# AC225-16A-MHCW05P-B_V1_0.net
KiCad netlist of a schematic drawn in Altium Designer
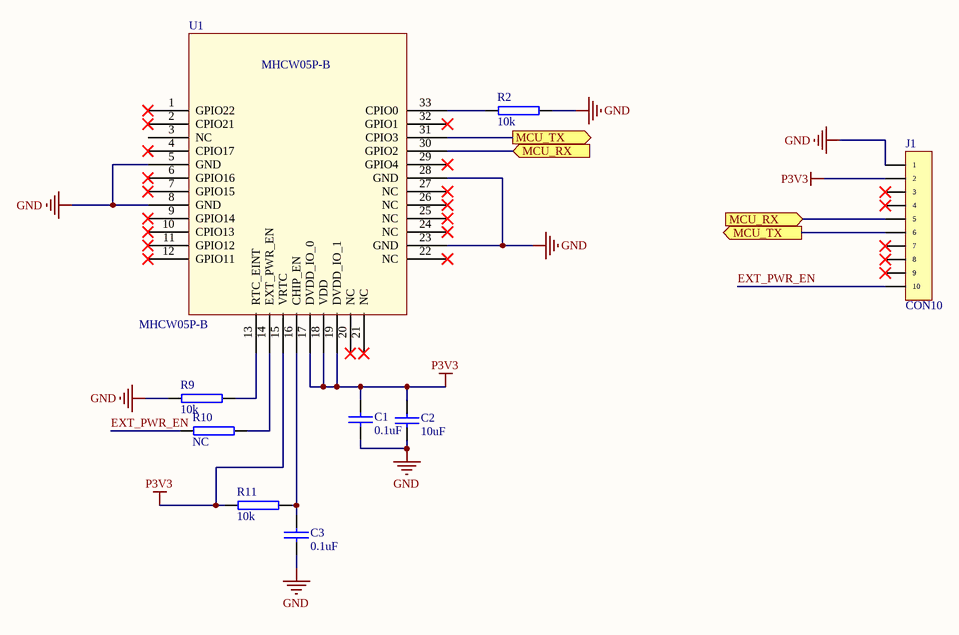
[diagram p0: AC225-16A-MHCW05P-B_V1.0.SchDoc]

(export (version "E")
  (design (tool "Eeschema 10.0.6"))
  (components
    (comp (ref "C1") (value "0.1uF") (footprint "C-0603") (libsource (lib "AOK 原理图库2020") (part "CAP")))
    (comp (ref "C2") (value "10uF") (footprint "C-0603") (libsource (lib "AOK 原理图库2020") (part "CAP")))
    (comp (ref "C3") (value "0.1uF") (footprint "C-0603") (libsource (lib "AOK 原理图库2020") (part "CAP")))
    (comp (ref "J1") (value "CON10") (footprint "DIP_10") (libsource (lib "AOK 原理图库2020") (part "CON10")))
    (comp (ref "R2") (value "10k") (footprint "R-0603") (libsource (lib "AOK 原理图库2020") (part "RES2")))
    (comp (ref "R9") (value "10k") (footprint "R-0603") (libsource (lib "AOK 原理图库2020") (part "RES2")))
    (comp (ref "R10") (value "NC") (footprint "R-0603") (libsource (lib "AOK 原理图库2020") (part "RES2")))
    (comp (ref "R11") (value "10k") (footprint "R-0603") (libsource (lib "AOK 原理图库2020") (part "RES2")))
    (comp (ref "U1")
      (value "MHCW05P-B")
      (footprint "MHCW05P-B")
      (libsource (lib "AOK 原理图库2020") (part "MHCW05P-B"))
    )
  )
  (nets
    (net (code "1") (name "/EXT_PWR_EN") (class "Default")
      (node (ref "J1") (pin "10") (pinfunction "10_10") (pintype "passive"))
      (node (ref "R10") (pin "2") (pinfunction "2_2") (pintype "passive"))
    )
    (net (code "2") (name "/MCU_RX") (class "Default")
      (node (ref "J1") (pin "5") (pinfunction "5_5") (pintype "passive"))
      (node (ref "U1") (pin "30") (pinfunction "GPIO2_30") (pintype "passive"))
    )
    (net (code "3") (name "/MCU_TX") (class "Default")
      (node (ref "J1") (pin "6") (pinfunction "6_6") (pintype "passive"))
      (node (ref "U1") (pin "31") (pinfunction "CPIO3_31") (pintype "passive"))
    )
    (net (code "4") (name "GND") (class "Default")
      (node (ref "C1") (pin "2") (pinfunction "2_2") (pintype "passive"))
      (node (ref "C2") (pin "2") (pinfunction "2_2") (pintype "passive"))
      (node (ref "C3") (pin "2") (pinfunction "2_2") (pintype "passive"))
      (node (ref "J1") (pin "1") (pinfunction "1_1") (pintype "passive"))
      (node (ref "R2") (pin "1") (pinfunction "1_1") (pintype "passive"))
      (node (ref "R9") (pin "2") (pinfunction "2_2") (pintype "passive"))
      (node (ref "U1") (pin "23") (pinfunction "GND_23") (pintype "passive"))
      (node (ref "U1") (pin "28") (pinfunction "GND_28") (pintype "passive"))
      (node (ref "U1") (pin "5") (pinfunction "GND_5") (pintype "passive"))
      (node (ref "U1") (pin "8") (pinfunction "GND_8") (pintype "passive"))
    )
    (net (code "5") (name "Net-(U1-CHIP_EN)") (class "Default")
      (node (ref "C3") (pin "1") (pinfunction "1_1") (pintype "passive"))
      (node (ref "R11") (pin "1") (pinfunction "1_1") (pintype "passive"))
      (node (ref "U1") (pin "16") (pinfunction "CHIP_EN_16") (pintype "passive"))
    )
    (net (code "6") (name "Net-(U1-CPIO0)") (class "Default")
      (node (ref "R2") (pin "2") (pinfunction "2_2") (pintype "passive"))
      (node (ref "U1") (pin "33") (pinfunction "CPIO0_33") (pintype "passive"))
    )
    (net (code "7") (name "Net-(U1-EXT_PWR_EN)") (class "Default")
      (node (ref "R10") (pin "1") (pinfunction "1_1") (pintype "passive"))
      (node (ref "U1") (pin "14") (pinfunction "EXT_PWR_EN_14") (pintype "passive"))
    )
    (net (code "8") (name "Net-(U1-RTC_EINT)") (class "Default")
      (node (ref "R9") (pin "1") (pinfunction "1_1") (pintype "passive"))
      (node (ref "U1") (pin "13") (pinfunction "RTC_EINT_13") (pintype "passive"))
    )
    (net (code "9") (name "P3V3") (class "Default")
      (node (ref "C1") (pin "1") (pinfunction "1_1") (pintype "passive"))
      (node (ref "C2") (pin "1") (pinfunction "1_1") (pintype "passive"))
      (node (ref "J1") (pin "2") (pinfunction "2_2") (pintype "passive"))
      (node (ref "R11") (pin "2") (pinfunction "2_2") (pintype "passive"))
      (node (ref "U1") (pin "15") (pinfunction "VRTC_15") (pintype "passive"))
      (node (ref "U1") (pin "17") (pinfunction "DVDD_IO_0_17") (pintype "passive"))
      (node (ref "U1") (pin "18") (pinfunction "VDD_18") (pintype "passive"))
      (node (ref "U1") (pin "19") (pinfunction "DVDD_IO_1_19") (pintype "passive"))
    )
    (net (code "10") (name "unconnected-(J1-Pad3)") (class "Default")
      (node (ref "J1") (pin "3") (pinfunction "3_3") (pintype "passive+no_connect"))
    )
    (net (code "11") (name "unconnected-(J1-Pad4)") (class "Default")
      (node (ref "J1") (pin "4") (pinfunction "4_4") (pintype "passive+no_connect"))
    )
    (net (code "12") (name "unconnected-(J1-Pad7)") (class "Default")
      (node (ref "J1") (pin "7") (pinfunction "7_7") (pintype "passive+no_connect"))
    )
    (net (code "13") (name "unconnected-(J1-Pad8)") (class "Default")
      (node (ref "J1") (pin "8") (pinfunction "8_8") (pintype "passive+no_connect"))
    )
    (net (code "14") (name "unconnected-(J1-Pad9)") (class "Default")
      (node (ref "J1") (pin "9") (pinfunction "9_9") (pintype "passive+no_connect"))
    )
    (net (code "15") (name "unconnected-(U1-CPIO13-Pad10)") (class "Default")
      (node (ref "U1") (pin "10") (pinfunction "CPIO13_10") (pintype "passive+no_connect"))
    )
    (net (code "16") (name "unconnected-(U1-CPIO17-Pad4)") (class "Default")
      (node (ref "U1") (pin "4") (pinfunction "CPIO17_4") (pintype "passive+no_connect"))
    )
    (net (code "17") (name "unconnected-(U1-CPIO21-Pad2)") (class "Default")
      (node (ref "U1") (pin "2") (pinfunction "CPIO21_2") (pintype "passive+no_connect"))
    )
    (net (code "18") (name "unconnected-(U1-GPIO1-Pad32)") (class "Default")
      (node (ref "U1") (pin "32") (pinfunction "GPIO1_32") (pintype "passive+no_connect"))
    )
    (net (code "19") (name "unconnected-(U1-GPIO4-Pad29)") (class "Default")
      (node (ref "U1") (pin "29") (pinfunction "GPIO4_29") (pintype "passive+no_connect"))
    )
    (net (code "20") (name "unconnected-(U1-GPIO11-Pad12)") (class "Default")
      (node (ref "U1") (pin "12") (pinfunction "GPIO11_12") (pintype "passive+no_connect"))
    )
    (net (code "21") (name "unconnected-(U1-GPIO12-Pad11)") (class "Default")
      (node (ref "U1") (pin "11") (pinfunction "GPIO12_11") (pintype "passive+no_connect"))
    )
    (net (code "22") (name "unconnected-(U1-GPIO14-Pad9)") (class "Default")
      (node (ref "U1") (pin "9") (pinfunction "GPIO14_9") (pintype "passive+no_connect"))
    )
    (net (code "23") (name "unconnected-(U1-GPIO15-Pad7)") (class "Default")
      (node (ref "U1") (pin "7") (pinfunction "GPIO15_7") (pintype "passive+no_connect"))
    )
    (net (code "24") (name "unconnected-(U1-GPIO16-Pad6)") (class "Default")
      (node (ref "U1") (pin "6") (pinfunction "GPIO16_6") (pintype "passive+no_connect"))
    )
    (net (code "25") (name "unconnected-(U1-GPIO22-Pad1)") (class "Default")
      (node (ref "U1") (pin "1") (pinfunction "GPIO22_1") (pintype "passive+no_connect"))
    )
    (net (code "26") (name "unconnected-(U1-NC-Pad3)") (class "Default")
      (node (ref "U1") (pin "3") (pinfunction "NC_3") (pintype "passive"))
    )
    (net (code "27") (name "unconnected-(U1-NC-Pad20)") (class "Default")
      (node (ref "U1") (pin "20") (pinfunction "NC_20") (pintype "passive+no_connect"))
    )
    (net (code "28") (name "unconnected-(U1-NC-Pad21)") (class "Default")
      (node (ref "U1") (pin "21") (pinfunction "NC_21") (pintype "passive+no_connect"))
    )
    (net (code "29") (name "unconnected-(U1-NC-Pad22)") (class "Default")
      (node (ref "U1") (pin "22") (pinfunction "NC_22") (pintype "passive+no_connect"))
    )
    (net (code "30") (name "unconnected-(U1-NC-Pad24)") (class "Default")
      (node (ref "U1") (pin "24") (pinfunction "NC_24") (pintype "passive+no_connect"))
    )
    (net (code "31") (name "unconnected-(U1-NC-Pad25)") (class "Default")
      (node (ref "U1") (pin "25") (pinfunction "NC_25") (pintype "passive+no_connect"))
    )
    (net (code "32") (name "unconnected-(U1-NC-Pad26)") (class "Default")
      (node (ref "U1") (pin "26") (pinfunction "NC_26") (pintype "passive+no_connect"))
    )
    (net (code "33") (name "unconnected-(U1-NC-Pad27)") (class "Default")
      (node (ref "U1") (pin "27") (pinfunction "NC_27") (pintype "passive+no_connect"))
    )
  )
)
